# airwisk_mosfet.net
KiCad netlist of a schematic drawn in EAGLE
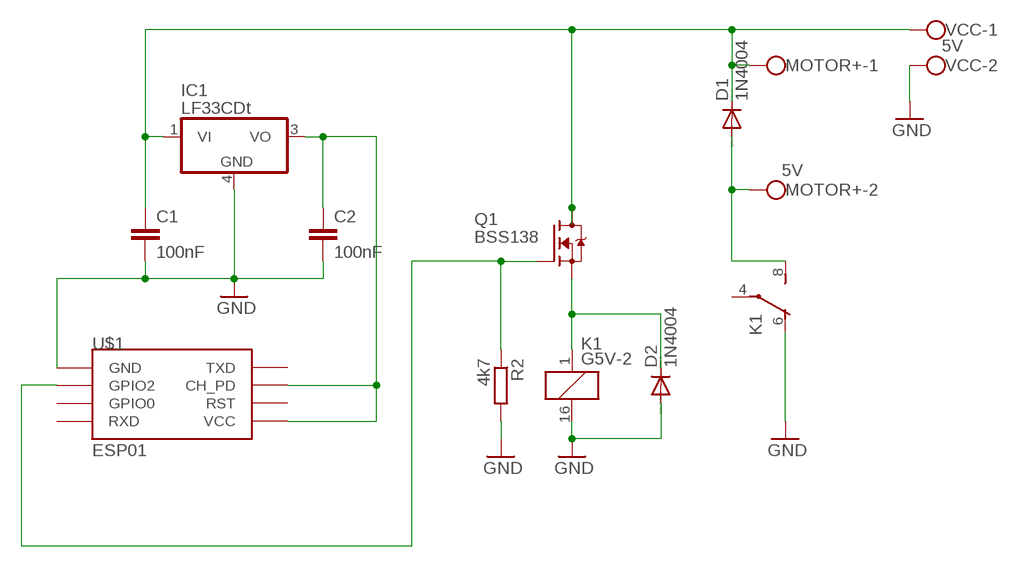
[diagram p0: schematic, sheet 1]

(export (version "E")
  (design (tool "Eeschema 10.0.6"))
  (components
    (comp (ref "C1")
      (value "100nF")
      (footprint "eagle-import:C025-025X050")
      (libsource (lib "eagle-import") (part "C-EU025-025X050"))
    )
    (comp (ref "C2")
      (value "100nF")
      (footprint "eagle-import:C025-025X050")
      (libsource (lib "eagle-import") (part "C-EU025-025X050"))
    )
    (comp (ref "D1")
      (value "1N4004")
      (footprint "eagle-import:DO41-10")
      (libsource (lib "eagle-import") (part "1N4004"))
    )
    (comp (ref "D2")
      (value "1N4004")
      (footprint "eagle-import:DO41-10")
      (libsource (lib "eagle-import") (part "1N4004"))
    )
    (comp (ref "IC1")
      (value "LF33CDt")
      (footprint "eagle-import:DPACK_3")
      (libsource (lib "eagle-import") (part "MC78M05ABDT"))
    )
    (comp (ref "K1")
      (value "G5V-2")
      (footprint "eagle-import:G5V-2")
      (fields (field (name "MPN") "G5V-2 5DC"))
      (libsource (lib "eagle-import") (part "G5V-2"))
    )
    (comp (ref "MOTOR+")
      (value "5V")
      (footprint "eagle-import:W237-102")
      (fields (field (name "MPN") "237-102"))
      (libsource (lib "eagle-import") (part "W237-102"))
    )
    (comp (ref "Q1")
      (value "BSS138")
      (footprint "eagle-import:SOT23")
      (fields (field (name "MF") "Fairchild"))
      (libsource (lib "eagle-import") (part "BSS138"))
    )
    (comp (ref "R2")
      (value "4k7")
      (footprint "eagle-import:0204_7")
      (libsource (lib "eagle-import") (part "R-EU_0204/7"))
    )
    (comp (ref "U$1")
      (value "ESP01")
      (footprint "eagle-import:ESP01")
      (libsource (lib "eagle-import") (part "ESP01"))
    )
    (comp (ref "VCC")
      (value "5V")
      (footprint "eagle-import:W237-102")
      (fields (field (name "MPN") "237-102"))
      (libsource (lib "eagle-import") (part "W237-102"))
    )
  )
  (nets
    (net (code "1") (name "GND") (class "Default")
      (node (ref "C1") (pin "2") (pinfunction "2_2") (pintype "passive"))
      (node (ref "C2") (pin "2") (pinfunction "2_2") (pintype "passive"))
      (node (ref "D2") (pin "A") (pinfunction "A_A") (pintype "passive"))
      (node (ref "IC1") (pin "4") (pinfunction "GND_4") (pintype "passive"))
      (node (ref "K1") (pin "16") (pinfunction "2_16") (pintype "passive"))
      (node (ref "K1") (pin "6") (pinfunction "O_6") (pintype "passive"))
      (node (ref "R2") (pin "2") (pinfunction "2_2") (pintype "passive"))
      (node (ref "U$1") (pin "GND") (pinfunction "GND_GND") (pintype "bidirectional"))
      (node (ref "VCC") (pin "2") (pinfunction "KL_2") (pintype "passive"))
    )
    (net (code "2") (name "Net-(IC1-VI)") (class "Default")
      (node (ref "C1") (pin "1") (pinfunction "1_1") (pintype "passive"))
      (node (ref "D1") (pin "C") (pinfunction "C_C") (pintype "passive"))
      (node (ref "IC1") (pin "1") (pinfunction "VI_1") (pintype "input"))
      (node (ref "MOTOR+") (pin "1") (pinfunction "KL_1") (pintype "passive"))
      (node (ref "Q1") (pin "3") (pinfunction "D_3") (pintype "passive"))
      (node (ref "VCC") (pin "1") (pinfunction "KL_1") (pintype "passive"))
    )
    (net (code "3") (name "Net-(IC1-VO)") (class "Default")
      (node (ref "C2") (pin "1") (pinfunction "1_1") (pintype "passive"))
      (node (ref "IC1") (pin "3") (pinfunction "VO_3") (pintype "passive"))
      (node (ref "U$1") (pin "CH_PD") (pinfunction "CH_PD_CH_PD") (pintype "bidirectional"))
      (node (ref "U$1") (pin "VCC") (pinfunction "VCC_VCC") (pintype "bidirectional"))
    )
    (net (code "4") (name "Net-(K1A-S)") (class "Default")
      (node (ref "D1") (pin "A") (pinfunction "A_A") (pintype "passive"))
      (node (ref "K1") (pin "8") (pinfunction "S_8") (pintype "passive"))
      (node (ref "MOTOR+") (pin "2") (pinfunction "KL_2") (pintype "passive"))
    )
    (net (code "5") (name "Net-(Q1-G)") (class "Default")
      (node (ref "Q1") (pin "1") (pinfunction "G_1") (pintype "passive"))
      (node (ref "R2") (pin "1") (pinfunction "1_1") (pintype "passive"))
      (node (ref "U$1") (pin "GPIO2") (pinfunction "GPIO2_GPIO2") (pintype "bidirectional"))
    )
    (net (code "6") (name "Net-(Q1-S)") (class "Default")
      (node (ref "D2") (pin "C") (pinfunction "C_C") (pintype "passive"))
      (node (ref "K1") (pin "1") (pinfunction "1_1") (pintype "passive"))
      (node (ref "Q1") (pin "2") (pinfunction "S_2") (pintype "passive"))
    )
    (net (code "7") (name "unconnected-(K1A-P-Pad4)") (class "Default")
      (node (ref "K1") (pin "4") (pinfunction "P_4") (pintype "passive"))
    )
    (net (code "8") (name "unconnected-(U$1-PadGPIO0)") (class "Default")
      (node (ref "U$1") (pin "GPIO0") (pinfunction "GPIO0_GPIO0") (pintype "bidirectional"))
    )
    (net (code "9") (name "unconnected-(U$1-PadRST)") (class "Default")
      (node (ref "U$1") (pin "RST") (pinfunction "RST_RST") (pintype "bidirectional"))
    )
    (net (code "10") (name "unconnected-(U$1-RXD-PadRX)") (class "Default")
      (node (ref "U$1") (pin "RX") (pinfunction "RXD_RX") (pintype "bidirectional"))
    )
    (net (code "11") (name "unconnected-(U$1-TXD-PadTX)") (class "Default")
      (node (ref "U$1") (pin "TX") (pinfunction "TXD_TX") (pintype "bidirectional"))
    )
  )
)
